# Voltage_Level_Translator_v3.net
KiCad netlist of a schematic drawn in Altium Designer
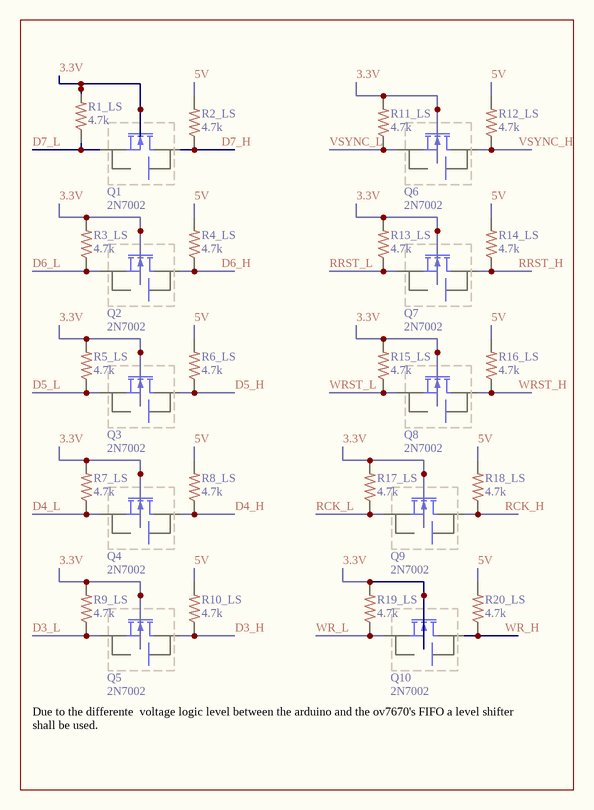
[diagram p0: Voltage_Level_Translator_v3.SchDoc]

(export (version "E")
  (design (tool "Eeschema 10.0.6"))
  (components
    (comp (ref "Q1")
      (value "2N7002")
      (footprint "SOT-23")
      (description "N-Channel MOSFET")
      (fields (field (name "PUBLISHER") "Altium Limited"))
      (libsource (lib "Trackuino_Shield") (part "MOSFET-N_MOD"))
    )
    (comp (ref "Q2")
      (value "2N7002")
      (footprint "SOT-23")
      (description "N-Channel MOSFET")
      (fields (field (name "PUBLISHER") "Altium Limited"))
      (libsource (lib "Trackuino_Shield") (part "MOSFET-N_MOD"))
    )
    (comp (ref "Q3")
      (value "2N7002")
      (footprint "SOT-23")
      (description "N-Channel MOSFET")
      (fields (field (name "PUBLISHER") "Altium Limited"))
      (libsource (lib "Trackuino_Shield") (part "MOSFET-N_MOD"))
    )
    (comp (ref "Q4")
      (value "2N7002")
      (footprint "SOT-23")
      (description "N-Channel MOSFET")
      (fields (field (name "PUBLISHER") "Altium Limited"))
      (libsource (lib "Trackuino_Shield") (part "MOSFET-N_MOD"))
    )
    (comp (ref "Q5")
      (value "2N7002")
      (footprint "SOT-23")
      (description "N-Channel MOSFET")
      (fields (field (name "PUBLISHER") "Altium Limited"))
      (libsource (lib "Trackuino_Shield") (part "MOSFET-N_MOD"))
    )
    (comp (ref "Q6")
      (value "2N7002")
      (footprint "SOT-23")
      (description "N-Channel MOSFET")
      (fields (field (name "PUBLISHER") "Altium Limited"))
      (libsource (lib "Trackuino_Shield") (part "MOSFET-N_MOD"))
    )
    (comp (ref "Q7")
      (value "2N7002")
      (footprint "SOT-23")
      (description "N-Channel MOSFET")
      (fields (field (name "PUBLISHER") "Altium Limited"))
      (libsource (lib "Trackuino_Shield") (part "MOSFET-N_MOD"))
    )
    (comp (ref "Q8")
      (value "2N7002")
      (footprint "SOT-23")
      (description "N-Channel MOSFET")
      (fields (field (name "PUBLISHER") "Altium Limited"))
      (libsource (lib "Trackuino_Shield") (part "MOSFET-N_MOD"))
    )
    (comp (ref "Q9")
      (value "2N7002")
      (footprint "SOT-23")
      (description "N-Channel MOSFET")
      (fields (field (name "PUBLISHER") "Altium Limited"))
      (libsource (lib "Trackuino_Shield") (part "MOSFET-N_MOD"))
    )
    (comp (ref "Q10")
      (value "2N7002")
      (footprint "SOT-23")
      (description "N-Channel MOSFET")
      (fields (field (name "PUBLISHER") "Altium Limited"))
      (libsource (lib "Trackuino_Shield") (part "MOSFET-N_MOD"))
    )
    (comp (ref "R1_LS")
      (value "4.7k")
      (footprint "0805")
      (libsource (lib "Trackuino_Shield") (part "0805RESISTOR"))
    )
    (comp (ref "R2_LS")
      (value "4.7k")
      (footprint "0805")
      (libsource (lib "Trackuino_Shield") (part "0805RESISTOR"))
    )
    (comp (ref "R3_LS")
      (value "4.7k")
      (footprint "0805")
      (libsource (lib "Trackuino_Shield") (part "0805RESISTOR"))
    )
    (comp (ref "R4_LS")
      (value "4.7k")
      (footprint "0805")
      (libsource (lib "Trackuino_Shield") (part "0805RESISTOR"))
    )
    (comp (ref "R5_LS")
      (value "4.7k")
      (footprint "0805")
      (libsource (lib "Trackuino_Shield") (part "0805RESISTOR"))
    )
    (comp (ref "R6_LS")
      (value "4.7k")
      (footprint "0805")
      (libsource (lib "Trackuino_Shield") (part "0805RESISTOR"))
    )
    (comp (ref "R7_LS")
      (value "4.7k")
      (footprint "0805")
      (libsource (lib "Trackuino_Shield") (part "0805RESISTOR"))
    )
    (comp (ref "R8_LS")
      (value "4.7k")
      (footprint "0805")
      (libsource (lib "Trackuino_Shield") (part "0805RESISTOR"))
    )
    (comp (ref "R9_LS")
      (value "4.7k")
      (footprint "0805")
      (libsource (lib "Trackuino_Shield") (part "0805RESISTOR"))
    )
    (comp (ref "R10_LS")
      (value "4.7k")
      (footprint "0805")
      (libsource (lib "Trackuino_Shield") (part "0805RESISTOR"))
    )
    (comp (ref "R11_LS")
      (value "4.7k")
      (footprint "0805")
      (libsource (lib "Trackuino_Shield") (part "0805RESISTOR"))
    )
    (comp (ref "R12_LS")
      (value "4.7k")
      (footprint "0805")
      (libsource (lib "Trackuino_Shield") (part "0805RESISTOR"))
    )
    (comp (ref "R13_LS")
      (value "4.7k")
      (footprint "0805")
      (libsource (lib "Trackuino_Shield") (part "0805RESISTOR"))
    )
    (comp (ref "R14_LS")
      (value "4.7k")
      (footprint "0805")
      (libsource (lib "Trackuino_Shield") (part "0805RESISTOR"))
    )
    (comp (ref "R15_LS")
      (value "4.7k")
      (footprint "0805")
      (libsource (lib "Trackuino_Shield") (part "0805RESISTOR"))
    )
    (comp (ref "R16_LS")
      (value "4.7k")
      (footprint "0805")
      (libsource (lib "Trackuino_Shield") (part "0805RESISTOR"))
    )
    (comp (ref "R17_LS")
      (value "4.7k")
      (footprint "0805")
      (libsource (lib "Trackuino_Shield") (part "0805RESISTOR"))
    )
    (comp (ref "R18_LS")
      (value "4.7k")
      (footprint "0805")
      (libsource (lib "Trackuino_Shield") (part "0805RESISTOR"))
    )
    (comp (ref "R19_LS")
      (value "4.7k")
      (footprint "0805")
      (libsource (lib "Trackuino_Shield") (part "0805RESISTOR"))
    )
    (comp (ref "R20_LS")
      (value "4.7k")
      (footprint "0805")
      (libsource (lib "Trackuino_Shield") (part "0805RESISTOR"))
    )
  )
  (nets
    (net (code "1") (name "/3.3V") (class "Default")
      (node (ref "Q1") (pin "2") (pinfunction "G_2") (pintype "passive"))
      (node (ref "Q10") (pin "2") (pinfunction "G_2") (pintype "passive"))
      (node (ref "Q2") (pin "2") (pinfunction "G_2") (pintype "passive"))
      (node (ref "Q3") (pin "2") (pinfunction "G_2") (pintype "passive"))
      (node (ref "Q4") (pin "2") (pinfunction "G_2") (pintype "passive"))
      (node (ref "Q5") (pin "2") (pinfunction "G_2") (pintype "passive"))
      (node (ref "Q6") (pin "2") (pinfunction "G_2") (pintype "passive"))
      (node (ref "Q7") (pin "2") (pinfunction "G_2") (pintype "passive"))
      (node (ref "Q8") (pin "2") (pinfunction "G_2") (pintype "passive"))
      (node (ref "Q9") (pin "2") (pinfunction "G_2") (pintype "passive"))
      (node (ref "R11_LS") (pin "2") (pinfunction "2_2") (pintype "passive"))
      (node (ref "R13_LS") (pin "2") (pinfunction "2_2") (pintype "passive"))
      (node (ref "R15_LS") (pin "2") (pinfunction "2_2") (pintype "passive"))
      (node (ref "R17_LS") (pin "2") (pinfunction "2_2") (pintype "passive"))
      (node (ref "R19_LS") (pin "2") (pinfunction "2_2") (pintype "passive"))
      (node (ref "R1_LS") (pin "2") (pinfunction "2_2") (pintype "passive"))
      (node (ref "R3_LS") (pin "2") (pinfunction "2_2") (pintype "passive"))
      (node (ref "R5_LS") (pin "2") (pinfunction "2_2") (pintype "passive"))
      (node (ref "R7_LS") (pin "2") (pinfunction "2_2") (pintype "passive"))
      (node (ref "R9_LS") (pin "2") (pinfunction "2_2") (pintype "passive"))
    )
    (net (code "2") (name "/5V") (class "Default")
      (node (ref "R10_LS") (pin "2") (pinfunction "2_2") (pintype "passive"))
      (node (ref "R12_LS") (pin "2") (pinfunction "2_2") (pintype "passive"))
      (node (ref "R14_LS") (pin "2") (pinfunction "2_2") (pintype "passive"))
      (node (ref "R16_LS") (pin "2") (pinfunction "2_2") (pintype "passive"))
      (node (ref "R18_LS") (pin "2") (pinfunction "2_2") (pintype "passive"))
      (node (ref "R20_LS") (pin "2") (pinfunction "2_2") (pintype "passive"))
      (node (ref "R2_LS") (pin "2") (pinfunction "2_2") (pintype "passive"))
      (node (ref "R4_LS") (pin "2") (pinfunction "2_2") (pintype "passive"))
      (node (ref "R6_LS") (pin "2") (pinfunction "2_2") (pintype "passive"))
      (node (ref "R8_LS") (pin "2") (pinfunction "2_2") (pintype "passive"))
    )
    (net (code "3") (name "/D3_H") (class "Default")
      (node (ref "Q5") (pin "1") (pinfunction "D_1") (pintype "passive"))
      (node (ref "R10_LS") (pin "1") (pinfunction "1_1") (pintype "passive"))
    )
    (net (code "4") (name "/D3_L") (class "Default")
      (node (ref "Q5") (pin "3") (pinfunction "S_3") (pintype "passive"))
      (node (ref "R9_LS") (pin "1") (pinfunction "1_1") (pintype "passive"))
    )
    (net (code "5") (name "/D4_H") (class "Default")
      (node (ref "Q4") (pin "1") (pinfunction "D_1") (pintype "passive"))
      (node (ref "R8_LS") (pin "1") (pinfunction "1_1") (pintype "passive"))
    )
    (net (code "6") (name "/D4_L") (class "Default")
      (node (ref "Q4") (pin "3") (pinfunction "S_3") (pintype "passive"))
      (node (ref "R7_LS") (pin "1") (pinfunction "1_1") (pintype "passive"))
    )
    (net (code "7") (name "/D5_H") (class "Default")
      (node (ref "Q3") (pin "1") (pinfunction "D_1") (pintype "passive"))
      (node (ref "R6_LS") (pin "1") (pinfunction "1_1") (pintype "passive"))
    )
    (net (code "8") (name "/D5_L") (class "Default")
      (node (ref "Q3") (pin "3") (pinfunction "S_3") (pintype "passive"))
      (node (ref "R5_LS") (pin "1") (pinfunction "1_1") (pintype "passive"))
    )
    (net (code "9") (name "/D6_H") (class "Default")
      (node (ref "Q2") (pin "1") (pinfunction "D_1") (pintype "passive"))
      (node (ref "R4_LS") (pin "1") (pinfunction "1_1") (pintype "passive"))
    )
    (net (code "10") (name "/D6_L") (class "Default")
      (node (ref "Q2") (pin "3") (pinfunction "S_3") (pintype "passive"))
      (node (ref "R3_LS") (pin "1") (pinfunction "1_1") (pintype "passive"))
    )
    (net (code "11") (name "/D7_H") (class "Default")
      (node (ref "Q1") (pin "1") (pinfunction "D_1") (pintype "passive"))
      (node (ref "R2_LS") (pin "1") (pinfunction "1_1") (pintype "passive"))
    )
    (net (code "12") (name "/D7_L") (class "Default")
      (node (ref "Q1") (pin "3") (pinfunction "S_3") (pintype "passive"))
      (node (ref "R1_LS") (pin "1") (pinfunction "1_1") (pintype "passive"))
    )
    (net (code "13") (name "/RCK_H") (class "Default")
      (node (ref "Q9") (pin "1") (pinfunction "D_1") (pintype "passive"))
      (node (ref "R18_LS") (pin "1") (pinfunction "1_1") (pintype "passive"))
    )
    (net (code "14") (name "/RCK_L") (class "Default")
      (node (ref "Q9") (pin "3") (pinfunction "S_3") (pintype "passive"))
      (node (ref "R17_LS") (pin "1") (pinfunction "1_1") (pintype "passive"))
    )
    (net (code "15") (name "/RRST_H") (class "Default")
      (node (ref "Q7") (pin "1") (pinfunction "D_1") (pintype "passive"))
      (node (ref "R14_LS") (pin "1") (pinfunction "1_1") (pintype "passive"))
    )
    (net (code "16") (name "/RRST_L") (class "Default")
      (node (ref "Q7") (pin "3") (pinfunction "S_3") (pintype "passive"))
      (node (ref "R13_LS") (pin "1") (pinfunction "1_1") (pintype "passive"))
    )
    (net (code "17") (name "/VSYNC_H") (class "Default")
      (node (ref "Q6") (pin "1") (pinfunction "D_1") (pintype "passive"))
      (node (ref "R12_LS") (pin "1") (pinfunction "1_1") (pintype "passive"))
    )
    (net (code "18") (name "/VSYNC_L") (class "Default")
      (node (ref "Q6") (pin "3") (pinfunction "S_3") (pintype "passive"))
      (node (ref "R11_LS") (pin "1") (pinfunction "1_1") (pintype "passive"))
    )
    (net (code "19") (name "/WRST_H") (class "Default")
      (node (ref "Q8") (pin "1") (pinfunction "D_1") (pintype "passive"))
      (node (ref "R16_LS") (pin "1") (pinfunction "1_1") (pintype "passive"))
    )
    (net (code "20") (name "/WRST_L") (class "Default")
      (node (ref "Q8") (pin "3") (pinfunction "S_3") (pintype "passive"))
      (node (ref "R15_LS") (pin "1") (pinfunction "1_1") (pintype "passive"))
    )
    (net (code "21") (name "/WR_H") (class "Default")
      (node (ref "Q10") (pin "1") (pinfunction "D_1") (pintype "passive"))
      (node (ref "R20_LS") (pin "1") (pinfunction "1_1") (pintype "passive"))
    )
    (net (code "22") (name "/WR_L") (class "Default")
      (node (ref "Q10") (pin "3") (pinfunction "S_3") (pintype "passive"))
      (node (ref "R19_LS") (pin "1") (pinfunction "1_1") (pintype "passive"))
    )
  )
)
